# puddingRemote.net
KiCad netlist of a schematic drawn in EAGLE
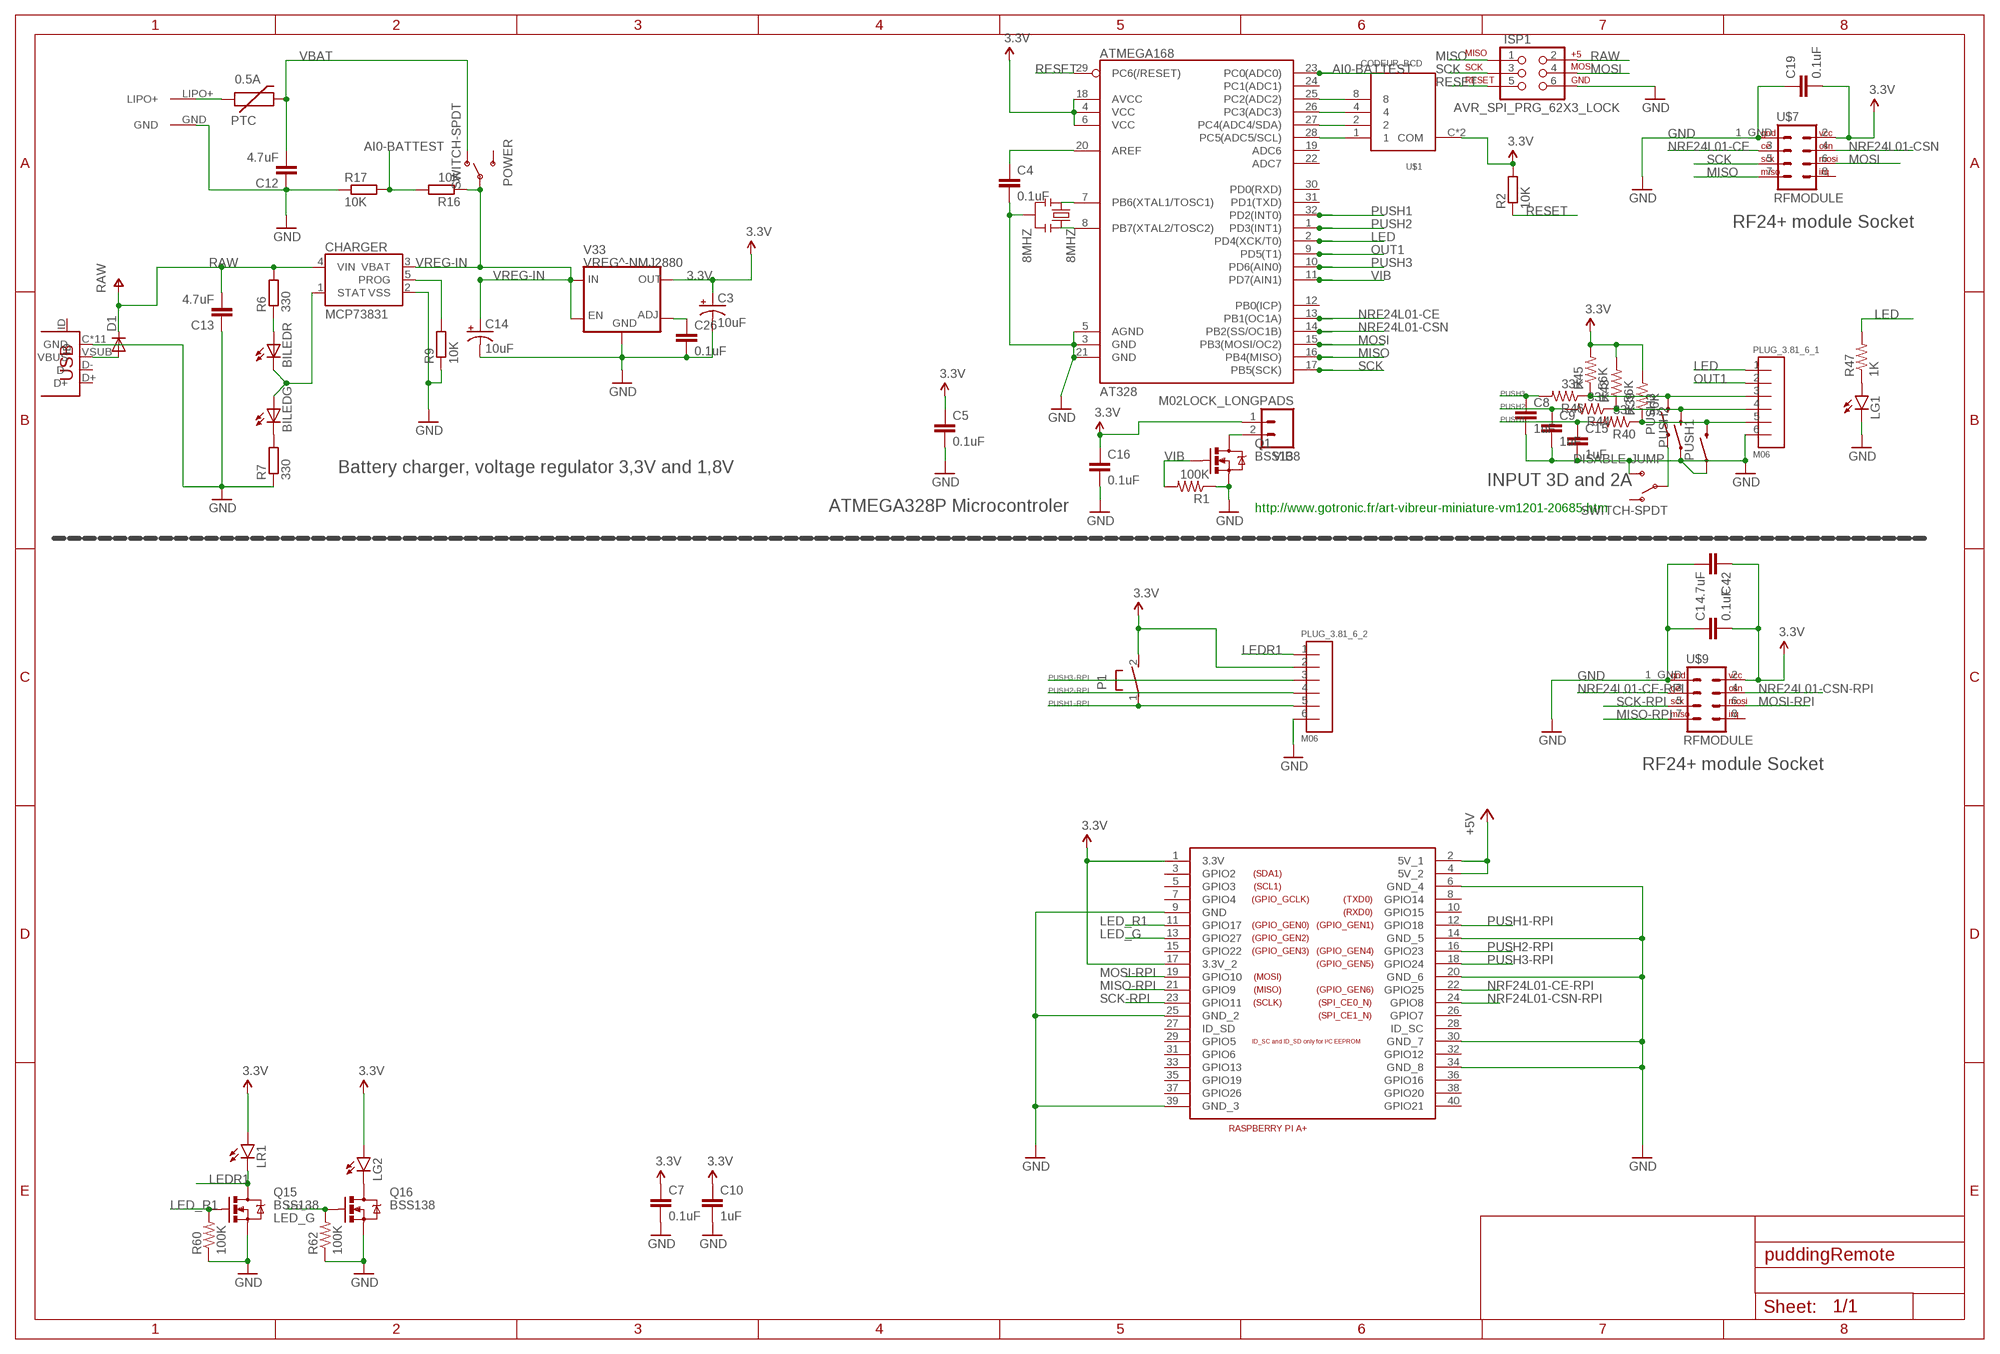
[diagram p0: schematic, sheet 1]

(export (version "E")
  (design (tool "Eeschema 10.0.6"))
  (components
    (comp (ref "0.5A")
      (value "PTC")
      (footprint "eagle-import:PTC-1210")
      (libsource (lib "eagle-import") (part "PTC"))
    )
    (comp (ref "8MHZ")
      (value "8MHZ")
      (footprint "eagle-import:RESONATOR-SMD")
      (libsource (lib "eagle-import") (part "RESONATOR8MHZ"))
    )
    (comp (ref "AT328")
      (value "ATMEGA168")
      (footprint "eagle-import:TQFP32-08")
      (libsource (lib "eagle-import") (part "ATMEGA168"))
    )
    (comp (ref "BILED")
      (value "BILED")
      (footprint "eagle-import:2XLED")
      (fields (field (name "OC_FARNELL") "5790888") (field (name "OC_RS") "6921278"))
      (libsource (lib "eagle-import") (part "BILED"))
    )
    (comp (ref "C1")
      (value "0.1uF")
      (footprint "eagle-import:C0603")
      (libsource (lib "eagle-import") (part "C-EUC0603"))
    )
    (comp (ref "C3")
      (value "10uF")
      (footprint "eagle-import:EIA3216")
      (libsource (lib "eagle-import") (part "CAP_POL1206"))
    )
    (comp (ref "C4")
      (value "0.1uF")
      (footprint "eagle-import:C0603")
      (libsource (lib "eagle-import") (part "C-EUC0603"))
    )
    (comp (ref "C5")
      (value "0.1uF")
      (footprint "eagle-import:C0603")
      (libsource (lib "eagle-import") (part "C-EUC0603"))
    )
    (comp (ref "C7")
      (value "0.1uF")
      (footprint "eagle-import:C0603")
      (libsource (lib "eagle-import") (part "C-EUC0603"))
    )
    (comp (ref "C8")
      (value "1uF")
      (footprint "eagle-import:C0603")
      (libsource (lib "eagle-import") (part "C-EUC0603"))
    )
    (comp (ref "C9")
      (value "1uF")
      (footprint "eagle-import:C0603")
      (libsource (lib "eagle-import") (part "C-EUC0603"))
    )
    (comp (ref "C10")
      (value "1uF")
      (footprint "eagle-import:C0603")
      (libsource (lib "eagle-import") (part "C-EUC0603"))
    )
    (comp (ref "C12")
      (value "4.7uF")
      (footprint "eagle-import:C0603")
      (libsource (lib "eagle-import") (part "C-EUC0603"))
    )
    (comp (ref "C13")
      (value "4.7uF")
      (footprint "eagle-import:C0603")
      (libsource (lib "eagle-import") (part "C-EUC0603"))
    )
    (comp (ref "C14")
      (value "10uF")
      (footprint "eagle-import:EIA3216")
      (libsource (lib "eagle-import") (part "CAP_POL1206"))
    )
    (comp (ref "C15")
      (value "1uF")
      (footprint "eagle-import:C0603")
      (libsource (lib "eagle-import") (part "C-EUC0603"))
    )
    (comp (ref "C16")
      (value "0.1uF")
      (footprint "eagle-import:C0603")
      (libsource (lib "eagle-import") (part "C-EUC0603"))
    )
    (comp (ref "C19")
      (value "0.1uF")
      (footprint "eagle-import:C0603")
      (libsource (lib "eagle-import") (part "C-EUC0603"))
    )
    (comp (ref "C26")
      (value "0.1uF")
      (footprint "eagle-import:C0603")
      (libsource (lib "eagle-import") (part "C-EUC0603"))
    )
    (comp (ref "C42")
      (value "4.7uF")
      (footprint "eagle-import:C0603")
      (libsource (lib "eagle-import") (part "C-EUC0603"))
    )
    (comp (ref "CHARGER")
      (value "MCP73831")
      (footprint "eagle-import:SOT23-5")
      (libsource (lib "eagle-import") (part "MCP73831"))
    )
    (comp (ref "D1")
      (value "DIODESMA-KIT")
      (footprint "eagle-import:SMA-DIODE-KIT")
      (libsource (lib "eagle-import") (part "DIODESMA-KIT"))
    )
    (comp (ref "DISABLE-JUMP")
      (value "SWITCH-SPDT")
      (footprint "eagle-import:SWITCH-102011SAQN")
      (libsource (lib "eagle-import") (part "SWITCH-SPDT"))
    )
    (comp (ref "ISP1")
      (value "AVR_SPI_PRG_62X3_LOCK")
      (footprint "eagle-import:2X3_LOCK")
      (libsource (lib "eagle-import") (part "AVR_SPI_PRG_62X3_LOCK"))
    )
    (comp (ref "LG1")
      (value "LED1206")
      (footprint "eagle-import:LED-1206")
      (libsource (lib "eagle-import") (part "LED1206"))
    )
    (comp (ref "LG2")
      (value "LED1206")
      (footprint "eagle-import:LED-1206")
      (libsource (lib "eagle-import") (part "LED1206"))
    )
    (comp (ref "LR1")
      (value "LED1206")
      (footprint "eagle-import:LED-1206")
      (libsource (lib "eagle-import") (part "LED1206"))
    )
    (comp (ref "P1")
      (value "31-XX")
      (footprint "eagle-import:B3F-31XX")
      (fields (field (name "MPN") "B3F-3100") (field (name "OC_FARNELL") "2079502"))
      (libsource (lib "eagle-import") (part "31-XX"))
    )
    (comp (ref "PLUG_3.81_6_1")
      (value "M06")
      (footprint "eagle-import:PLUG_06")
      (libsource (lib "eagle-import") (part "M06"))
    )
    (comp (ref "PLUG_3.81_6_2")
      (value "M06")
      (footprint "eagle-import:PLUG_06")
      (libsource (lib "eagle-import") (part "M06"))
    )
    (comp (ref "POWER")
      (value "SWITCH-SPDT")
      (footprint "eagle-import:SWITCH-102011SAQN")
      (libsource (lib "eagle-import") (part "SWITCH-SPDT"))
    )
    (comp (ref "PUSH1")
      (value "SWITCH-MOMENTARY-2PTH")
      (footprint "eagle-import:TACTILE-PTH")
      (libsource (lib "eagle-import") (part "SWITCH-MOMENTARY-2PTH"))
    )
    (comp (ref "PUSH2")
      (value "SWITCH-MOMENTARY-2PTH")
      (footprint "eagle-import:TACTILE-PTH")
      (libsource (lib "eagle-import") (part "SWITCH-MOMENTARY-2PTH"))
    )
    (comp (ref "PUSH3")
      (value "SWITCH-MOMENTARY-2PTH")
      (footprint "eagle-import:TACTILE-PTH")
      (libsource (lib "eagle-import") (part "SWITCH-MOMENTARY-2PTH"))
    )
    (comp (ref "Q1")
      (value "BSS138")
      (footprint "eagle-import:SOT23-3")
      (libsource (lib "eagle-import") (part "MOSFET-NCHANNELBSS138"))
    )
    (comp (ref "Q15")
      (value "BSS138")
      (footprint "eagle-import:SOT23-3")
      (libsource (lib "eagle-import") (part "MOSFET-NCHANNELBSS138"))
    )
    (comp (ref "Q16")
      (value "BSS138")
      (footprint "eagle-import:SOT23-3")
      (libsource (lib "eagle-import") (part "MOSFET-NCHANNELBSS138"))
    )
    (comp (ref "R1")
      (value "100K")
      (footprint "eagle-import:0603-RES")
      (libsource (lib "eagle-import") (part "RESISTOR0603-RES"))
    )
    (comp (ref "R2")
      (value "10K")
      (footprint "eagle-import:R0603")
      (libsource (lib "eagle-import") (part "R-EU_R0603"))
    )
    (comp (ref "R6")
      (value "330")
      (footprint "eagle-import:R0603")
      (libsource (lib "eagle-import") (part "R-EU_R0603"))
    )
    (comp (ref "R7")
      (value "330")
      (footprint "eagle-import:R0603")
      (libsource (lib "eagle-import") (part "R-EU_R0603"))
    )
    (comp (ref "R9")
      (value "10K")
      (footprint "eagle-import:R0603")
      (libsource (lib "eagle-import") (part "R-EU_R0603"))
    )
    (comp (ref "R16")
      (value "10K")
      (footprint "eagle-import:R0603")
      (libsource (lib "eagle-import") (part "R-EU_R0603"))
    )
    (comp (ref "R17")
      (value "10K")
      (footprint "eagle-import:R0603")
      (libsource (lib "eagle-import") (part "R-EU_R0603"))
    )
    (comp (ref "R39")
      (value "56K")
      (footprint "eagle-import:0603-RES")
      (libsource (lib "eagle-import") (part "RESISTOR0603-RES"))
    )
    (comp (ref "R40")
      (value "33K")
      (footprint "eagle-import:0603-RES")
      (libsource (lib "eagle-import") (part "RESISTOR0603-RES"))
    )
    (comp (ref "R43")
      (value "56K")
      (footprint "eagle-import:0603-RES")
      (libsource (lib "eagle-import") (part "RESISTOR0603-RES"))
    )
    (comp (ref "R44")
      (value "33K")
      (footprint "eagle-import:0603-RES")
      (libsource (lib "eagle-import") (part "RESISTOR0603-RES"))
    )
    (comp (ref "R45")
      (value "56K")
      (footprint "eagle-import:0603-RES")
      (libsource (lib "eagle-import") (part "RESISTOR0603-RES"))
    )
    (comp (ref "R46")
      (value "33K")
      (footprint "eagle-import:0603-RES")
      (libsource (lib "eagle-import") (part "RESISTOR0603-RES"))
    )
    (comp (ref "R47")
      (value "1K")
      (footprint "eagle-import:0603-RES")
      (libsource (lib "eagle-import") (part "RESISTOR0603-RES"))
    )
    (comp (ref "R60")
      (value "100K")
      (footprint "eagle-import:0603-RES")
      (libsource (lib "eagle-import") (part "RESISTOR0603-RES"))
    )
    (comp (ref "R62")
      (value "100K")
      (footprint "eagle-import:0603-RES")
      (libsource (lib "eagle-import") (part "RESISTOR0603-RES"))
    )
    (comp (ref "U$1")
      (value "CODEUR_BCD")
      (footprint "eagle-import:MCRM4HAF-10R-V-B")
      (libsource (lib "eagle-import") (part "CODEUR_BCD"))
    )
    (comp (ref "U$2")
      (value "USB-MICROB")
      (footprint "eagle-import:USB-MICROB-10103594-0001LF")
      (libsource (lib "eagle-import") (part "USB-MICROB"))
    )
    (comp (ref "U$4")
      (value "RASPIRASPIB")
      (footprint "eagle-import:RASPIB")
      (libsource (lib "eagle-import") (part "RASPIRASPIB"))
    )
    (comp (ref "U$7")
      (value "RFMODULE")
      (footprint "eagle-import:2X5_RFMODULE")
      (libsource (lib "eagle-import") (part "RFMODULE"))
    )
    (comp (ref "U$8")
      (value "LIPO_PAD")
      (footprint "eagle-import:2X1_LIPO_PAD")
      (libsource (lib "eagle-import") (part "LIPO_PAD"))
    )
    (comp (ref "U$9")
      (value "RFMODULE")
      (footprint "eagle-import:2X5_RFMODULE")
      (libsource (lib "eagle-import") (part "RFMODULE"))
    )
    (comp (ref "V33")
      (value "VREG^-NMJ2880")
      (footprint "eagle-import:SOT-89")
      (libsource (lib "eagle-import") (part "VREG^-NMJ2880"))
    )
    (comp (ref "VIB")
      (value "M02LOCK_LONGPADS")
      (footprint "eagle-import:1X02_LOCK_LONGPADS")
      (libsource (lib "eagle-import") (part "M02LOCK_LONGPADS"))
    )
  )
  (nets
    (net (code "1") (name "+5V") (class "Default")
      (node (ref "U$4") (pin "2") (pinfunction "5V_1_2") (pintype "bidirectional"))
      (node (ref "U$4") (pin "4") (pinfunction "5V_2_4") (pintype "bidirectional"))
    )
    (net (code "2") (name "/AI0-BATTEST") (class "Default")
      (node (ref "AT328") (pin "23") (pinfunction "PC0(ADC0)_23") (pintype "bidirectional"))
      (node (ref "R16") (pin "2") (pinfunction "2_2") (pintype "passive"))
      (node (ref "R17") (pin "2") (pinfunction "2_2") (pintype "passive"))
    )
    (net (code "3") (name "/LED") (class "Default")
      (node (ref "AT328") (pin "2") (pinfunction "PD4(XCK/T0)_2") (pintype "bidirectional"))
      (node (ref "PLUG_3.81_6_1") (pin "1") (pinfunction "1_1") (pintype "bidirectional"))
      (node (ref "R47") (pin "2") (pinfunction "2_2") (pintype "passive"))
    )
    (net (code "4") (name "/LEDR1") (class "Default")
      (node (ref "LR1") (pin "C") (pinfunction "C_C") (pintype "passive"))
      (node (ref "PLUG_3.81_6_2") (pin "1") (pinfunction "1_1") (pintype "bidirectional"))
      (node (ref "Q15") (pin "3") (pinfunction "D_3") (pintype "passive"))
    )
    (net (code "5") (name "/LED_G") (class "Default")
      (node (ref "Q16") (pin "1") (pinfunction "G_1") (pintype "passive"))
      (node (ref "R62") (pin "2") (pinfunction "2_2") (pintype "passive"))
      (node (ref "U$4") (pin "13") (pinfunction "GPIO27_13") (pintype "bidirectional"))
    )
    (net (code "6") (name "/LED_R1") (class "Default")
      (node (ref "Q15") (pin "1") (pinfunction "G_1") (pintype "passive"))
      (node (ref "R60") (pin "2") (pinfunction "2_2") (pintype "passive"))
      (node (ref "U$4") (pin "11") (pinfunction "GPIO17_11") (pintype "bidirectional"))
    )
    (net (code "7") (name "/MISO") (class "Default")
      (node (ref "AT328") (pin "16") (pinfunction "PB4(MISO)_16") (pintype "bidirectional"))
      (node (ref "ISP1") (pin "1") (pinfunction "1_1") (pintype "passive"))
      (node (ref "U$7") (pin "7") (pinfunction "MISO_7") (pintype "passive"))
    )
    (net (code "8") (name "/MISO-RPI") (class "Default")
      (node (ref "U$4") (pin "21") (pinfunction "GPIO9_21") (pintype "bidirectional"))
      (node (ref "U$9") (pin "7") (pinfunction "MISO_7") (pintype "passive"))
    )
    (net (code "9") (name "/MOSI") (class "Default")
      (node (ref "AT328") (pin "15") (pinfunction "PB3(MOSI/OC2)_15") (pintype "bidirectional"))
      (node (ref "ISP1") (pin "4") (pinfunction "4_4") (pintype "passive"))
      (node (ref "U$7") (pin "6") (pinfunction "MOSI_6") (pintype "passive"))
    )
    (net (code "10") (name "/MOSI-RPI") (class "Default")
      (node (ref "U$4") (pin "19") (pinfunction "GPIO10_19") (pintype "bidirectional"))
      (node (ref "U$9") (pin "6") (pinfunction "MOSI_6") (pintype "passive"))
    )
    (net (code "11") (name "/NRF24L01-CE") (class "Default")
      (node (ref "AT328") (pin "13") (pinfunction "PB1(OC1A)_13") (pintype "bidirectional"))
      (node (ref "U$7") (pin "3") (pinfunction "CE_3") (pintype "passive"))
    )
    (net (code "12") (name "/NRF24L01-CE-RPI") (class "Default")
      (node (ref "U$4") (pin "22") (pinfunction "GPIO25_22") (pintype "bidirectional"))
      (node (ref "U$9") (pin "3") (pinfunction "CE_3") (pintype "passive"))
    )
    (net (code "13") (name "/NRF24L01-CSN") (class "Default")
      (node (ref "AT328") (pin "14") (pinfunction "PB2(SS/OC1B)_14") (pintype "bidirectional"))
      (node (ref "U$7") (pin "4") (pinfunction "CSN_4") (pintype "passive"))
    )
    (net (code "14") (name "/NRF24L01-CSN-RPI") (class "Default")
      (node (ref "U$4") (pin "24") (pinfunction "GPIO8_24") (pintype "bidirectional"))
      (node (ref "U$9") (pin "4") (pinfunction "CSN_4") (pintype "passive"))
    )
    (net (code "15") (name "/OUT1") (class "Default")
      (node (ref "AT328") (pin "9") (pinfunction "PD5(T1)_9") (pintype "bidirectional"))
      (node (ref "PLUG_3.81_6_1") (pin "2") (pinfunction "2_2") (pintype "bidirectional"))
    )
    (net (code "16") (name "/PUSH1") (class "Default")
      (node (ref "AT328") (pin "32") (pinfunction "PD2(INT0)_32") (pintype "bidirectional"))
      (node (ref "C15") (pin "1") (pinfunction "1_1") (pintype "passive"))
      (node (ref "R40") (pin "2") (pinfunction "2_2") (pintype "passive"))
    )
    (net (code "17") (name "/PUSH1-RPI") (class "Default")
      (node (ref "P1") (pin "1") (pinfunction "P_1") (pintype "passive"))
      (node (ref "PLUG_3.81_6_2") (pin "5") (pinfunction "5_5") (pintype "bidirectional"))
      (node (ref "U$4") (pin "12") (pinfunction "GPIO18_12") (pintype "bidirectional"))
    )
    (net (code "18") (name "/PUSH2") (class "Default")
      (node (ref "AT328") (pin "1") (pinfunction "PD3(INT1)_1") (pintype "bidirectional"))
      (node (ref "C9") (pin "1") (pinfunction "1_1") (pintype "passive"))
      (node (ref "R44") (pin "2") (pinfunction "2_2") (pintype "passive"))
    )
    (net (code "19") (name "/PUSH2-RPI") (class "Default")
      (node (ref "PLUG_3.81_6_2") (pin "4") (pinfunction "4_4") (pintype "bidirectional"))
      (node (ref "U$4") (pin "16") (pinfunction "GPIO23_16") (pintype "bidirectional"))
    )
    (net (code "20") (name "/PUSH3") (class "Default")
      (node (ref "AT328") (pin "10") (pinfunction "PD6(AIN0)_10") (pintype "bidirectional"))
      (node (ref "C8") (pin "1") (pinfunction "1_1") (pintype "passive"))
      (node (ref "R46") (pin "2") (pinfunction "2_2") (pintype "passive"))
    )
    (net (code "21") (name "/PUSH3-RPI") (class "Default")
      (node (ref "PLUG_3.81_6_2") (pin "3") (pinfunction "3_3") (pintype "bidirectional"))
      (node (ref "U$4") (pin "18") (pinfunction "GPIO24_18") (pintype "bidirectional"))
    )
    (net (code "22") (name "/RESET") (class "Default")
      (node (ref "AT328") (pin "29") (pinfunction "PC6(/RESET)_29") (pintype "bidirectional"))
      (node (ref "ISP1") (pin "5") (pinfunction "5_5") (pintype "passive"))
      (node (ref "R2") (pin "1") (pinfunction "1_1") (pintype "passive"))
    )
    (net (code "23") (name "/SCK") (class "Default")
      (node (ref "AT328") (pin "17") (pinfunction "PB5(SCK)_17") (pintype "bidirectional"))
      (node (ref "ISP1") (pin "3") (pinfunction "3_3") (pintype "passive"))
      (node (ref "U$7") (pin "5") (pinfunction "SCK_5") (pintype "passive"))
    )
    (net (code "24") (name "/SCK-RPI") (class "Default")
      (node (ref "U$4") (pin "23") (pinfunction "GPIO11_23") (pintype "bidirectional"))
      (node (ref "U$9") (pin "5") (pinfunction "SCK_5") (pintype "passive"))
    )
    (net (code "25") (name "/VBAT") (class "Default")
      (node (ref "0.5A") (pin "2") (pinfunction "2_2") (pintype "bidirectional"))
      (node (ref "C12") (pin "2") (pinfunction "2_2") (pintype "passive"))
      (node (ref "POWER") (pin "1") (pinfunction "O_1") (pintype "passive"))
    )
    (net (code "26") (name "/VIB") (class "Default")
      (node (ref "AT328") (pin "11") (pinfunction "PD7(AIN1)_11") (pintype "bidirectional"))
      (node (ref "Q1") (pin "1") (pinfunction "G_1") (pintype "passive"))
      (node (ref "R1") (pin "2") (pinfunction "2_2") (pintype "passive"))
    )
    (net (code "27") (name "/VREG-IN") (class "Default")
      (node (ref "C14") (pin "A") (pinfunction "+_A") (pintype "passive"))
      (node (ref "CHARGER") (pin "3") (pinfunction "VBAT_3") (pintype "power_in"))
      (node (ref "POWER") (pin "C") (pinfunction "P_C") (pintype "passive"))
      (node (ref "R16") (pin "1") (pinfunction "1_1") (pintype "passive"))
      (node (ref "V33") (pin "1") (pinfunction "EN_1") (pintype "bidirectional"))
      (node (ref "V33") (pin "5") (pinfunction "IN_5") (pintype "input"))
    )
    (net (code "28") (name "3.3V") (class "Default")
      (node (ref "AT328") (pin "18") (pinfunction "AVCC_18") (pintype "bidirectional"))
      (node (ref "AT328") (pin "4") (pinfunction "VCC_4") (pintype "bidirectional"))
      (node (ref "AT328") (pin "6") (pinfunction "VCC_6") (pintype "bidirectional"))
      (node (ref "C1") (pin "2") (pinfunction "2_2") (pintype "passive"))
      (node (ref "C10") (pin "1") (pinfunction "1_1") (pintype "passive"))
      (node (ref "C16") (pin "1") (pinfunction "1_1") (pintype "passive"))
      (node (ref "C19") (pin "2") (pinfunction "2_2") (pintype "passive"))
      (node (ref "C3") (pin "A") (pinfunction "+_A") (pintype "passive"))
      (node (ref "C42") (pin "1") (pinfunction "1_1") (pintype "passive"))
      (node (ref "C5") (pin "1") (pinfunction "1_1") (pintype "passive"))
      (node (ref "C7") (pin "1") (pinfunction "1_1") (pintype "passive"))
      (node (ref "LG2") (pin "A") (pinfunction "A_A") (pintype "passive"))
      (node (ref "LR1") (pin "A") (pinfunction "A_A") (pintype "passive"))
      (node (ref "P1") (pin "2") (pinfunction "S_2") (pintype "passive"))
      (node (ref "PLUG_3.81_6_2") (pin "2") (pinfunction "2_2") (pintype "bidirectional"))
      (node (ref "R2") (pin "2") (pinfunction "2_2") (pintype "passive"))
      (node (ref "R39") (pin "2") (pinfunction "2_2") (pintype "passive"))
      (node (ref "R43") (pin "2") (pinfunction "2_2") (pintype "passive"))
      (node (ref "R45") (pin "2") (pinfunction "2_2") (pintype "passive"))
      (node (ref "U$1") (pin "C") (pinfunction "COM_C") (pintype "bidirectional"))
      (node (ref "U$1") (pin "C2") (pinfunction "COM_C2") (pintype "bidirectional"))
      (node (ref "U$4") (pin "1") (pinfunction "3.3V_1") (pintype "bidirectional"))
      (node (ref "U$4") (pin "17") (pinfunction "3.3V_2_17") (pintype "bidirectional"))
      (node (ref "U$7") (pin "2") (pinfunction "VCC_2") (pintype "passive"))
      (node (ref "U$9") (pin "2") (pinfunction "VCC_2") (pintype "passive"))
      (node (ref "V33") (pin "4") (pinfunction "OUT_4") (pintype "output"))
      (node (ref "VIB") (pin "1") (pinfunction "1_1") (pintype "passive"))
    )
    (net (code "29") (name "GND") (class "Default")
      (node (ref "8MHZ") (pin "2") (pinfunction "2_2") (pintype "passive"))
      (node (ref "AT328") (pin "21") (pinfunction "GND_21") (pintype "bidirectional"))
      (node (ref "AT328") (pin "3") (pinfunction "GND_3") (pintype "bidirectional"))
      (node (ref "AT328") (pin "5") (pinfunction "AGND_5") (pintype "bidirectional"))
      (node (ref "C1") (pin "1") (pinfunction "1_1") (pintype "passive"))
      (node (ref "C10") (pin "2") (pinfunction "2_2") (pintype "passive"))
      (node (ref "C12") (pin "1") (pinfunction "1_1") (pintype "passive"))
      (node (ref "C13") (pin "1") (pinfunction "1_1") (pintype "passive"))
      (node (ref "C14") (pin "C") (pinfunction "-_C") (pintype "passive"))
      (node (ref "C15") (pin "2") (pinfunction "2_2") (pintype "passive"))
      (node (ref "C16") (pin "2") (pinfunction "2_2") (pintype "passive"))
      (node (ref "C19") (pin "1") (pinfunction "1_1") (pintype "passive"))
      (node (ref "C26") (pin "2") (pinfunction "2_2") (pintype "passive"))
      (node (ref "C3") (pin "C") (pinfunction "-_C") (pintype "passive"))
      (node (ref "C4") (pin "2") (pinfunction "2_2") (pintype "passive"))
      (node (ref "C42") (pin "2") (pinfunction "2_2") (pintype "passive"))
      (node (ref "C5") (pin "2") (pinfunction "2_2") (pintype "passive"))
      (node (ref "C7") (pin "2") (pinfunction "2_2") (pintype "passive"))
      (node (ref "C8") (pin "2") (pinfunction "2_2") (pintype "passive"))
      (node (ref "C9") (pin "2") (pinfunction "2_2") (pintype "passive"))
      (node (ref "CHARGER") (pin "2") (pinfunction "VSS_2") (pintype "power_in"))
      (node (ref "DISABLE-JUMP") (pin "3") (pinfunction "S_3") (pintype "passive"))
      (node (ref "ISP1") (pin "6") (pinfunction "6_6") (pintype "passive"))
      (node (ref "LG1") (pin "C") (pinfunction "C_C") (pintype "passive"))
      (node (ref "PLUG_3.81_6_1") (pin "6") (pinfunction "6_6") (pintype "bidirectional"))
      (node (ref "PLUG_3.81_6_2") (pin "6") (pinfunction "6_6") (pintype "bidirectional"))
      (node (ref "PUSH1") (pin "1") (pinfunction "1_1") (pintype "passive"))
      (node (ref "PUSH2") (pin "1") (pinfunction "1_1") (pintype "passive"))
      (node (ref "Q1") (pin "2") (pinfunction "S_2") (pintype "passive"))
      (node (ref "Q15") (pin "2") (pinfunction "S_2") (pintype "passive"))
      (node (ref "Q16") (pin "2") (pinfunction "S_2") (pintype "passive"))
      (node (ref "R1") (pin "1") (pinfunction "1_1") (pintype "passive"))
      (node (ref "R17") (pin "1") (pinfunction "1_1") (pintype "passive"))
      (node (ref "R60") (pin "1") (pinfunction "1_1") (pintype "passive"))
      (node (ref "R62") (pin "1") (pinfunction "1_1") (pintype "passive"))
      (node (ref "R7") (pin "1") (pinfunction "1_1") (pintype "passive"))
      (node (ref "R9") (pin "1") (pinfunction "1_1") (pintype "passive"))
      (node (ref "U$2") (pin "C") (pinfunction "GND_C") (pintype "bidirectional"))
      (node (ref "U$2") (pin "C1") (pinfunction "GND_C1") (pintype "bidirectional"))
      (node (ref "U$2") (pin "C3") (pinfunction "GND_C3") (pintype "bidirectional"))
      (node (ref "U$2") (pin "C4") (pinfunction "GND_C4") (pintype "bidirectional"))
      (node (ref "U$2") (pin "C5") (pinfunction "GND_C5") (pintype "bidirectional"))
      (node (ref "U$2") (pin "C6") (pinfunction "GND_C6") (pintype "bidirectional"))
      (node (ref "U$2") (pin "GND") (pinfunction "GND_GND") (pintype "bidirectional"))
      (node (ref "U$2") (pin "P$1") (pinfunction "GND_P$1") (pintype "bidirectional"))
      (node (ref "U$2") (pin "P$2") (pinfunction "GND_P$2") (pintype "bidirectional"))
      (node (ref "U$2") (pin "P$3") (pinfunction "GND_P$3") (pintype "bidirectional"))
      (node (ref "U$2") (pin "P$4") (pinfunction "GND_P$4") (pintype "bidirectional"))
      (node (ref "U$4") (pin "14") (pinfunction "GND_5_14") (pintype "bidirectional"))
      (node (ref "U$4") (pin "20") (pinfunction "GND_6_20") (pintype "bidirectional"))
      (node (ref "U$4") (pin "25") (pinfunction "GND_2_25") (pintype "bidirectional"))
      (node (ref "U$4") (pin "30") (pinfunction "GND_7_30") (pintype "bidirectional"))
      (node (ref "U$4") (pin "34") (pinfunction "GND_8_34") (pintype "bidirectional"))
      (node (ref "U$4") (pin "39") (pinfunction "GND_3_39") (pintype "bidirectional"))
      (node (ref "U$4") (pin "6") (pinfunction "GND_4_6") (pintype "bidirectional"))
      (node (ref "U$4") (pin "9") (pinfunction "GND_9") (pintype "bidirectional"))
      (node (ref "U$7") (pin "1_GND") (pinfunction "GND_1_GND") (pintype "passive"))
      (node (ref "U$8") (pin "GND") (pinfunction "GND_GND") (pintype "bidirectional"))
      (node (ref "U$9") (pin "1_GND") (pinfunction "GND_1_GND") (pintype "passive"))
      (node (ref "V33") (pin "2") (pinfunction "GND_2") (pintype "bidirectional"))
    )
    (net (code "30") (name "Net-(0.5A-Pad1)") (class "Default")
      (node (ref "0.5A") (pin "1") (pinfunction "1_1") (pintype "bidirectional"))
      (node (ref "U$8") (pin "LIPO+") (pinfunction "LIPO+_LIPO+") (pintype "bidirectional"))
    )
    (net (code "31") (name "Net-(AT328-AREF)") (class "Default")
      (node (ref "AT328") (pin "20") (pinfunction "AREF_20") (pintype "bidirectional"))
      (node (ref "C4") (pin "1") (pinfunction "1_1") (pintype "passive"))
    )
    (net (code "32") (name "Net-(AT328-PB6(XTAL1{slash}TOSC1))") (class "Default")
      (node (ref "8MHZ") (pin "1") (pinfunction "1_1") (pintype "passive"))
      (node (ref "AT328") (pin "7") (pinfunction "PB6(XTAL1/TOSC1)_7") (pintype "bidirectional"))
    )
    (net (code "33") (name "Net-(AT328-PB7(XTAL2{slash}TOSC2))") (class "Default")
      (node (ref "8MHZ") (pin "3") (pinfunction "3_3") (pintype "passive"))
      (node (ref "AT328") (pin "8") (pinfunction "PB7(XTAL2/TOSC2)_8") (pintype "bidirectional"))
    )
    (net (code "34") (name "Net-(AT328-PC2(ADC2))") (class "Default")
      (node (ref "AT328") (pin "25") (pinfunction "PC2(ADC2)_25") (pintype "bidirectional"))
      (node (ref "U$1") (pin "8") (pinfunction "8_8") (pintype "bidirectional"))
    )
    (net (code "35") (name "Net-(AT328-PC3(ADC3))") (class "Default")
      (node (ref "AT328") (pin "26") (pinfunction "PC3(ADC3)_26") (pintype "bidirectional"))
      (node (ref "U$1") (pin "4") (pinfunction "4_4") (pintype "bidirectional"))
    )
    (net (code "36") (name "Net-(AT328-PC4(ADC4{slash}SDA))") (class "Default")
      (node (ref "AT328") (pin "27") (pinfunction "PC4(ADC4/SDA)_27") (pintype "bidirectional"))
      (node (ref "U$1") (pin "2") (pinfunction "2_2") (pintype "bidirectional"))
    )
    (net (code "37") (name "Net-(AT328-PC5(ADC5{slash}SCL))") (class "Default")
      (node (ref "AT328") (pin "28") (pinfunction "PC5(ADC5/SCL)_28") (pintype "bidirectional"))
      (node (ref "U$1") (pin "1") (pinfunction "1_1") (pintype "bidirectional"))
    )
    (net (code "38") (name "Net-(BILEDA-A)") (class "Default")
      (node (ref "BILED") (pin "A1") (pinfunction "A_A1") (pintype "passive"))
      (node (ref "BILED") (pin "C4") (pinfunction "C_C4") (pintype "passive"))
      (node (ref "CHARGER") (pin "1") (pinfunction "STAT_1") (pintype "output"))
    )
    (net (code "39") (name "Net-(BILEDA-C)") (class "Default")
      (node (ref "BILED") (pin "C3") (pinfunction "C_C3") (pintype "passive"))
      (node (ref "R7") (pin "2") (pinfunction "2_2") (pintype "passive"))
    )
    (net (code "40") (name "Net-(BILEDB-A)") (class "Default")
      (node (ref "BILED") (pin "A2") (pinfunction "A_A2") (pintype "passive"))
      (node (ref "R6") (pin "1") (pinfunction "1_1") (pintype "passive"))
    )
    (net (code "41") (name "Net-(CHARGER-PROG)") (class "Default")
      (node (ref "CHARGER") (pin "5") (pinfunction "PROG_5") (pintype "input"))
      (node (ref "R9") (pin "2") (pinfunction "2_2") (pintype "passive"))
    )
    (net (code "42") (name "Net-(DISABLE-JUMP-P)") (class "Default")
      (node (ref "DISABLE-JUMP") (pin "C") (pinfunction "P_C") (pintype "passive"))
      (node (ref "PUSH3") (pin "1") (pinfunction "1_1") (pintype "passive"))
    )
    (net (code "43") (name "Net-(LG1-PadA)") (class "Default")
      (node (ref "LG1") (pin "A") (pinfunction "A_A") (pintype "passive"))
      (node (ref "R47") (pin "1") (pinfunction "1_1") (pintype "passive"))
    )
    (net (code "44") (name "Net-(PUSH1-2)") (class "Default")
      (node (ref "PLUG_3.81_6_1") (pin "5") (pinfunction "5_5") (pintype "bidirectional"))
      (node (ref "PUSH1") (pin "3") (pinfunction "2_3") (pintype "passive"))
      (node (ref "R39") (pin "1") (pinfunction "1_1") (pintype "passive"))
      (node (ref "R40") (pin "1") (pinfunction "1_1") (pintype "passive"))
    )
    (net (code "45") (name "Net-(PUSH2-2)") (class "Default")
      (node (ref "PLUG_3.81_6_1") (pin "4") (pinfunction "4_4") (pintype "bidirectional"))
      (node (ref "PUSH2") (pin "3") (pinfunction "2_3") (pintype "passive"))
      (node (ref "R43") (pin "1") (pinfunction "1_1") (pintype "passive"))
      (node (ref "R44") (pin "1") (pinfunction "1_1") (pintype "passive"))
    )
    (net (code "46") (name "Net-(PUSH3-2)") (class "Default")
      (node (ref "PLUG_3.81_6_1") (pin "3") (pinfunction "3_3") (pintype "bidirectional"))
      (node (ref "PUSH3") (pin "3") (pinfunction "2_3") (pintype "passive"))
      (node (ref "R45") (pin "1") (pinfunction "1_1") (pintype "passive"))
      (node (ref "R46") (pin "1") (pinfunction "1_1") (pintype "passive"))
    )
    (net (code "47") (name "Net-(Q1-D)") (class "Default")
      (node (ref "Q1") (pin "3") (pinfunction "D_3") (pintype "passive"))
      (node (ref "VIB") (pin "2") (pinfunction "2_2") (pintype "passive"))
    )
    (net (code "48") (name "Net-(Q16-D)") (class "Default")
      (node (ref "LG2") (pin "C") (pinfunction "C_C") (pintype "passive"))
      (node (ref "Q16") (pin "3") (pinfunction "D_3") (pintype "passive"))
    )
    (net (code "49") (name "Net-(U$2-VBUS)") (class "Default")
      (node (ref "D1") (pin "A") (pinfunction "A_A") (pintype "passive"))
      (node (ref "U$2") (pin "VSUB") (pinfunction "VBUS_VSUB") (pintype "bidirectional"))
    )
    (net (code "50") (name "Net-(V33-ADJ)") (class "Default")
      (node (ref "C26") (pin "1") (pinfunction "1_1") (pintype "passive"))
      (node (ref "V33") (pin "3") (pinfunction "ADJ_3") (pintype "input"))
    )
    (net (code "51") (name "RAW") (class "Default")
      (node (ref "C13") (pin "2") (pinfunction "2_2") (pintype "passive"))
      (node (ref "CHARGER") (pin "4") (pinfunction "VIN_4") (pintype "power_in"))
      (node (ref "D1") (pin "C") (pinfunction "C_C") (pintype "passive"))
      (node (ref "ISP1") (pin "2") (pinfunction "2_2") (pintype "passive"))
      (node (ref "R6") (pin "2") (pinfunction "2_2") (pintype "passive"))
    )
    (net (code "52") (name "unconnected-(AT328-ADC6-Pad19)") (class "Default")
      (node (ref "AT328") (pin "19") (pinfunction "ADC6_19") (pintype "bidirectional"))
    )
    (net (code "53") (name "unconnected-(AT328-ADC7-Pad22)") (class "Default")
      (node (ref "AT328") (pin "22") (pinfunction "ADC7_22") (pintype "bidirectional"))
    )
    (net (code "54") (name "unconnected-(AT328-PB0(ICP)-Pad12)") (class "Default")
      (node (ref "AT328") (pin "12") (pinfunction "PB0(ICP)_12") (pintype "bidirectional"))
    )
    (net (code "55") (name "unconnected-(AT328-PC1(ADC1)-Pad24)") (class "Default")
      (node (ref "AT328") (pin "24") (pinfunction "PC1(ADC1)_24") (pintype "bidirectional"))
    )
    (net (code "56") (name "unconnected-(AT328-PD0(RXD)-Pad30)") (class "Default")
      (node (ref "AT328") (pin "30") (pinfunction "PD0(RXD)_30") (pintype "bidirectional"))
    )
    (net (code "57") (name "unconnected-(AT328-PD1(TXD)-Pad31)") (class "Default")
      (node (ref "AT328") (pin "31") (pinfunction "PD1(TXD)_31") (pintype "bidirectional"))
    )
    (net (code "58") (name "unconnected-(DISABLE-JUMP-O-Pad1)") (class "Default")
      (node (ref "DISABLE-JUMP") (pin "1") (pinfunction "O_1") (pintype "passive"))
    )
    (net (code "59") (name "unconnected-(POWER-S-Pad3)") (class "Default")
      (node (ref "POWER") (pin "3") (pinfunction "S_3") (pintype "passive"))
    )
    (net (code "60") (name "unconnected-(U$2-PadD+)") (class "Default")
      (node (ref "U$2") (pin "D+") (pinfunction "D+_D+") (pintype "bidirectional"))
    )
    (net (code "61") (name "unconnected-(U$2-PadD-)") (class "Default")
      (node (ref "U$2") (pin "D-") (pinfunction "D-_D-") (pintype "bidirectional"))
    )
    (net (code "62") (name "unconnected-(U$2-PadID)") (class "Default")
      (node (ref "U$2") (pin "ID") (pinfunction "ID_ID") (pintype "bidirectional"))
    )
    (net (code "63") (name "unconnected-(U$4-GPIO2-Pad3)") (class "Default")
      (node (ref "U$4") (pin "3") (pinfunction "GPIO2_3") (pintype "bidirectional"))
    )
    (net (code "64") (name "unconnected-(U$4-GPIO3-Pad5)") (class "Default")
      (node (ref "U$4") (pin "5") (pinfunction "GPIO3_5") (pintype "bidirectional"))
    )
    (net (code "65") (name "unconnected-(U$4-GPIO4-Pad7)") (class "Default")
      (node (ref "U$4") (pin "7") (pinfunction "GPIO4_7") (pintype "bidirectional"))
    )
    (net (code "66") (name "unconnected-(U$4-GPIO5-Pad29)") (class "Default")
      (node (ref "U$4") (pin "29") (pinfunction "GPIO5_29") (pintype "bidirectional"))
    )
    (net (code "67") (name "unconnected-(U$4-GPIO6-Pad31)") (class "Default")
      (node (ref "U$4") (pin "31") (pinfunction "GPIO6_31") (pintype "bidirectional"))
    )
    (net (code "68") (name "unconnected-(U$4-GPIO7-Pad26)") (class "Default")
      (node (ref "U$4") (pin "26") (pinfunction "GPIO7_26") (pintype "bidirectional"))
    )
    (net (code "69") (name "unconnected-(U$4-GPIO12-Pad32)") (class "Default")
      (node (ref "U$4") (pin "32") (pinfunction "GPIO12_32") (pintype "bidirectional"))
    )
    (net (code "70") (name "unconnected-(U$4-GPIO13-Pad33)") (class "Default")
      (node (ref "U$4") (pin "33") (pinfunction "GPIO13_33") (pintype "bidirectional"))
    )
    (net (code "71") (name "unconnected-(U$4-GPIO14-Pad8)") (class "Default")
      (node (ref "U$4") (pin "8") (pinfunction "GPIO14_8") (pintype "bidirectional"))
    )
    (net (code "72") (name "unconnected-(U$4-GPIO15-Pad10)") (class "Default")
      (node (ref "U$4") (pin "10") (pinfunction "GPIO15_10") (pintype "bidirectional"))
    )
    (net (code "73") (name "unconnected-(U$4-GPIO16-Pad36)") (class "Default")
      (node (ref "U$4") (pin "36") (pinfunction "GPIO16_36") (pintype "bidirectional"))
    )
    (net (code "74") (name "unconnected-(U$4-GPIO19-Pad35)") (class "Default")
      (node (ref "U$4") (pin "35") (pinfunction "GPIO19_35") (pintype "bidirectional"))
    )
    (net (code "75") (name "unconnected-(U$4-GPIO20-Pad38)") (class "Default")
      (node (ref "U$4") (pin "38") (pinfunction "GPIO20_38") (pintype "bidirectional"))
    )
    (net (code "76") (name "unconnected-(U$4-GPIO21-Pad40)") (class "Default")
      (node (ref "U$4") (pin "40") (pinfunction "GPIO21_40") (pintype "bidirectional"))
    )
    (net (code "77") (name "unconnected-(U$4-GPIO22-Pad15)") (class "Default")
      (node (ref "U$4") (pin "15") (pinfunction "GPIO22_15") (pintype "bidirectional"))
    )
    (net (code "78") (name "unconnected-(U$4-GPIO26-Pad37)") (class "Default")
      (node (ref "U$4") (pin "37") (pinfunction "GPIO26_37") (pintype "bidirectional"))
    )
    (net (code "79") (name "unconnected-(U$4-ID_SC-Pad28)") (class "Default")
      (node (ref "U$4") (pin "28") (pinfunction "ID_SC_28") (pintype "bidirectional"))
    )
    (net (code "80") (name "unconnected-(U$4-ID_SD-Pad27)") (class "Default")
      (node (ref "U$4") (pin "27") (pinfunction "ID_SD_27") (pintype "bidirectional"))
    )
    (net (code "81") (name "unconnected-(U$7-IRQ-Pad8)") (class "Default")
      (node (ref "U$7") (pin "8") (pinfunction "IRQ_8") (pintype "passive"))
    )
    (net (code "82") (name "unconnected-(U$9-IRQ-Pad8)") (class "Default")
      (node (ref "U$9") (pin "8") (pinfunction "IRQ_8") (pintype "passive"))
    )
  )
)
